# lcr_meter1.net
KiCad netlist of a schematic drawn in EAGLE
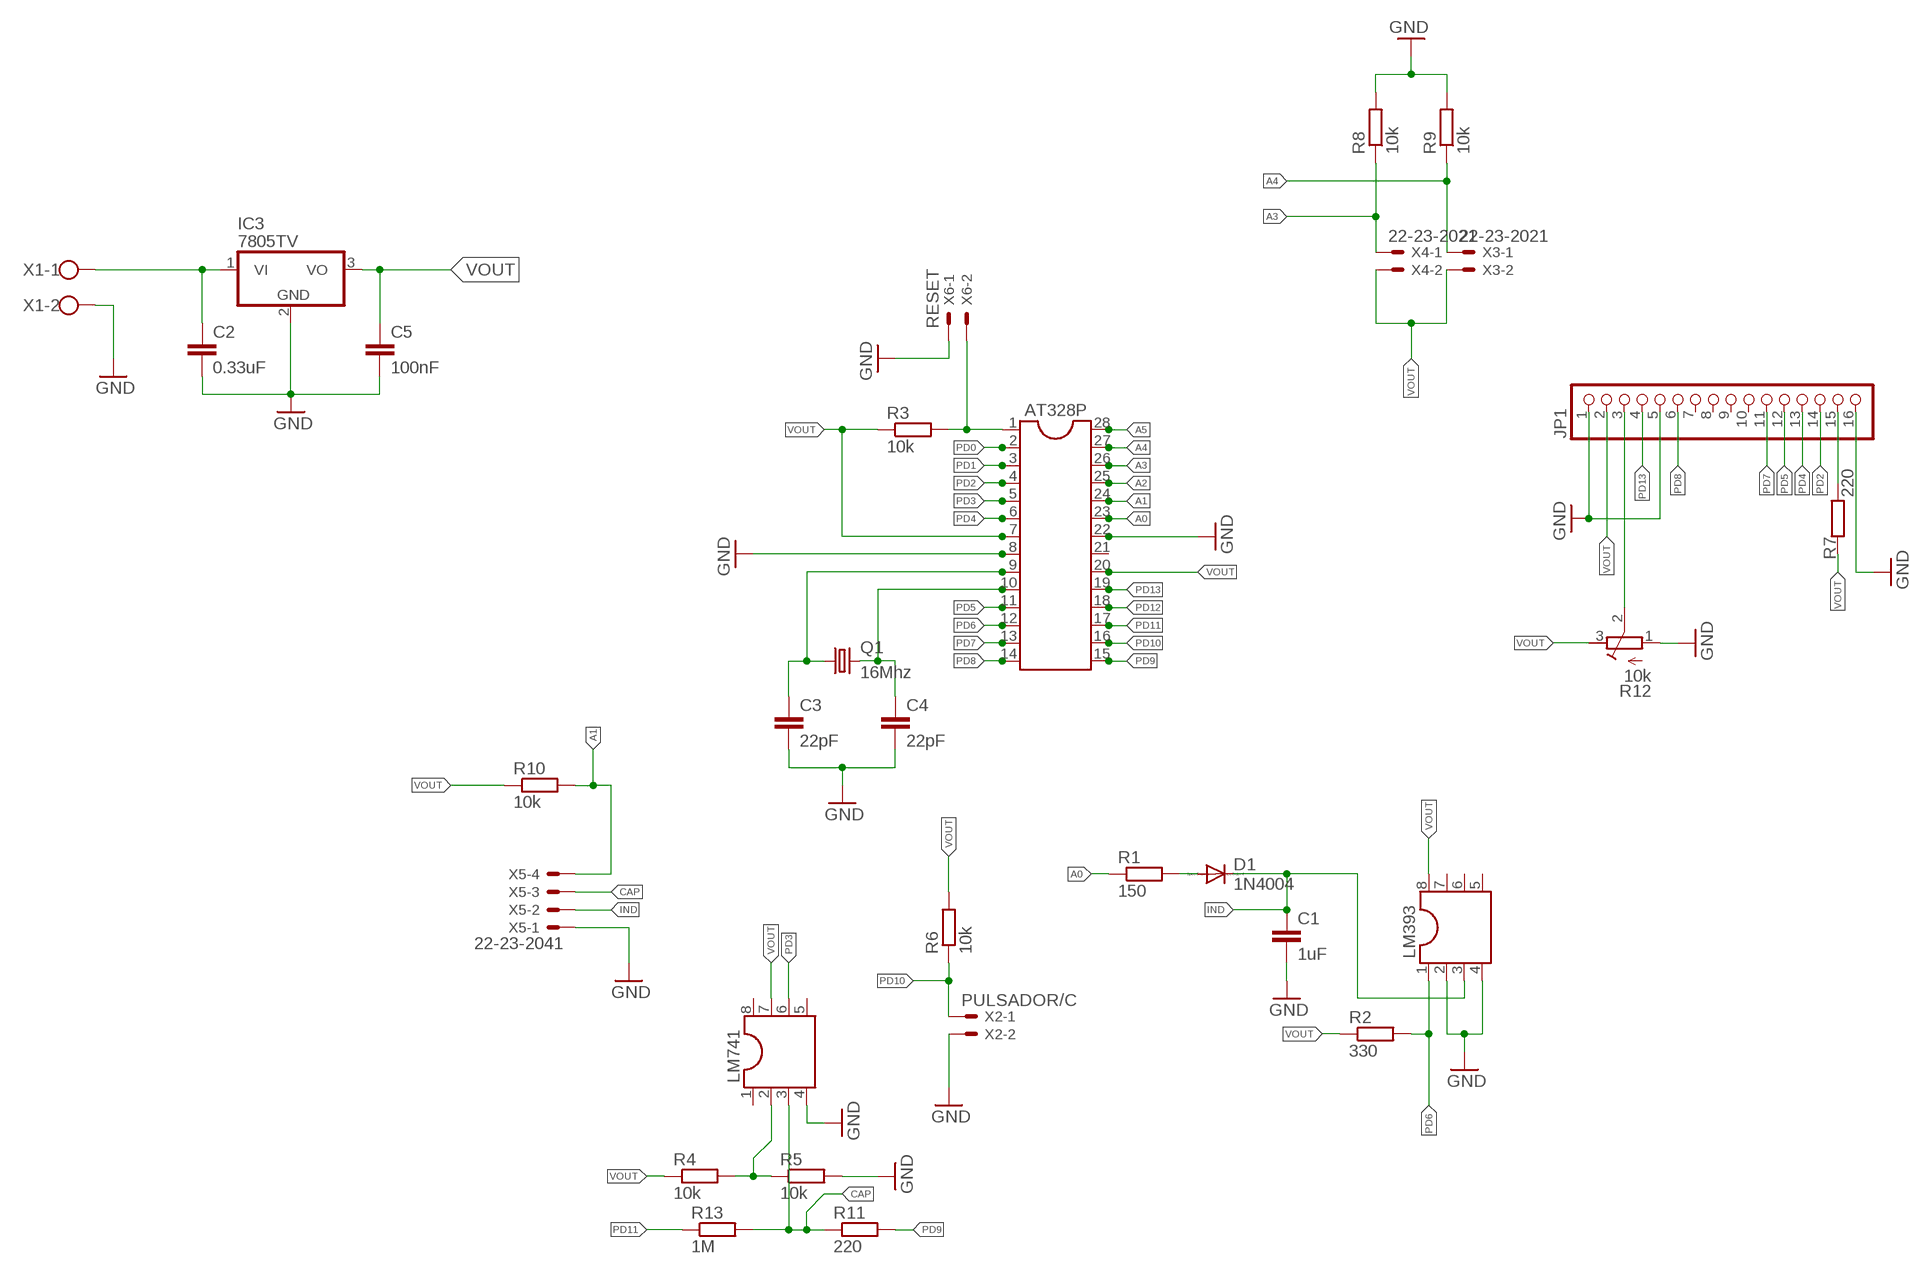
[diagram p0: schematic, sheet 1]

(export (version "E")
  (design (tool "Eeschema 10.0.6"))
  (components
    (comp (ref "AT328P")
      (value "DIL28-3")
      (footprint "eagle-import:DIL28-3")
      (libsource (lib "eagle-import") (part "DIL28-3"))
    )
    (comp (ref "C1")
      (value "1uF")
      (footprint "eagle-import:C050-024X044")
      (libsource (lib "eagle-import") (part "C-EU050-024X044"))
    )
    (comp (ref "C2")
      (value "0.33uF")
      (footprint "eagle-import:C050-024X044")
      (libsource (lib "eagle-import") (part "C-EU050-024X044"))
    )
    (comp (ref "C3")
      (value "22pF")
      (footprint "eagle-import:C025-030X050")
      (libsource (lib "eagle-import") (part "C-EU025-030X050"))
    )
    (comp (ref "C4")
      (value "22pF")
      (footprint "eagle-import:C025-030X050")
      (libsource (lib "eagle-import") (part "C-EU025-030X050"))
    )
    (comp (ref "C5")
      (value "100nF")
      (footprint "eagle-import:C025-030X050")
      (libsource (lib "eagle-import") (part "C-EU025-030X050"))
    )
    (comp (ref "D1")
      (value "1N4004")
      (footprint "eagle-import:DO41-10")
      (libsource (lib "eagle-import") (part "1N4004"))
    )
    (comp (ref "IC3")
      (value "7805TV")
      (footprint "eagle-import:TO220V")
      (libsource (lib "eagle-import") (part "78TV05"))
    )
    (comp (ref "JP1")
      (value "PINHD-1X16")
      (footprint "eagle-import:1X16")
      (libsource (lib "eagle-import") (part "PINHD-1X16"))
    )
    (comp (ref "LM393")
      (value "DIL8S")
      (footprint "eagle-import:SOCKET-08")
      (libsource (lib "eagle-import") (part "DIL8S"))
    )
    (comp (ref "LM741")
      (value "DIL8S")
      (footprint "eagle-import:SOCKET-08")
      (libsource (lib "eagle-import") (part "DIL8S"))
    )
    (comp (ref "Q1")
      (value "16Mhz")
      (footprint "eagle-import:HC49_S")
      (libsource (lib "eagle-import") (part "CRYSTALHC49S"))
    )
    (comp (ref "R1")
      (value "150")
      (footprint "eagle-import:0207_7")
      (libsource (lib "eagle-import") (part "R-EU_0207/7"))
    )
    (comp (ref "R2")
      (value "330")
      (footprint "eagle-import:0207_7")
      (libsource (lib "eagle-import") (part "R-EU_0207/7"))
    )
    (comp (ref "R3")
      (value "10k")
      (footprint "eagle-import:0207_7")
      (libsource (lib "eagle-import") (part "R-EU_0207/7"))
    )
    (comp (ref "R4")
      (value "10k")
      (footprint "eagle-import:0207_7")
      (libsource (lib "eagle-import") (part "R-EU_0207/7"))
    )
    (comp (ref "R5")
      (value "10k")
      (footprint "eagle-import:0207_7")
      (libsource (lib "eagle-import") (part "R-EU_0207/7"))
    )
    (comp (ref "R6")
      (value "10k")
      (footprint "eagle-import:0207_7")
      (libsource (lib "eagle-import") (part "R-EU_0207/7"))
    )
    (comp (ref "R7")
      (value "220")
      (footprint "eagle-import:0207_7")
      (libsource (lib "eagle-import") (part "R-EU_0207/7"))
    )
    (comp (ref "R8")
      (value "10k")
      (footprint "eagle-import:0207_7")
      (libsource (lib "eagle-import") (part "R-EU_0207/7"))
    )
    (comp (ref "R9")
      (value "10k")
      (footprint "eagle-import:0207_7")
      (libsource (lib "eagle-import") (part "R-EU_0207/7"))
    )
    (comp (ref "R10")
      (value "10k")
      (footprint "eagle-import:0207_7")
      (libsource (lib "eagle-import") (part "R-EU_0207/7"))
    )
    (comp (ref "R11")
      (value "220")
      (footprint "eagle-import:0207_7")
      (libsource (lib "eagle-import") (part "R-EU_0207/7"))
    )
    (comp (ref "R12")
      (value "10k")
      (footprint "eagle-import:RTRIM64W")
      (libsource (lib "eagle-import") (part "R-TRIMM64W"))
    )
    (comp (ref "R13")
      (value "1M")
      (footprint "eagle-import:0207_7")
      (libsource (lib "eagle-import") (part "R-EU_0207/7"))
    )
    (comp (ref "X1")
      (value "W237-102")
      (footprint "eagle-import:W237-102")
      (fields (field (name "MPN") "237-102"))
      (libsource (lib "eagle-import") (part "W237-102"))
    )
    (comp (ref "X2")
      (value "PULSADOR/C")
      (footprint "eagle-import:22-23-2021")
      (fields (field (name "MF") "MOLEX") (field (name "MPN") "22-23-2021"))
      (libsource (lib "eagle-import") (part "22-23-2021"))
    )
    (comp (ref "X3")
      (value "22-23-2021")
      (footprint "eagle-import:22-23-2021")
      (fields (field (name "MF") "MOLEX"))
      (libsource (lib "eagle-import") (part "22-23-2021"))
    )
    (comp (ref "X4")
      (value "22-23-2021")
      (footprint "eagle-import:22-23-2021")
      (fields (field (name "MF") "MOLEX"))
      (libsource (lib "eagle-import") (part "22-23-2021"))
    )
    (comp (ref "X5")
      (value "22-23-2041")
      (footprint "eagle-import:22-23-2041")
      (fields (field (name "MF") "MOLEX"))
      (libsource (lib "eagle-import") (part "22-23-2041"))
    )
    (comp (ref "X6")
      (value "RESET")
      (footprint "eagle-import:22-23-2021")
      (fields (field (name "MF") "MOLEX") (field (name "MPN") "22-23-2021"))
      (libsource (lib "eagle-import") (part "22-23-2021"))
    )
  )
  (nets
    (net (code "1") (name "A0") (class "Default")
      (node (ref "AT328P") (pin "23") (pinfunction "23_23") (pintype "passive"))
      (node (ref "R1") (pin "1") (pinfunction "1_1") (pintype "passive"))
    )
    (net (code "2") (name "A1") (class "Default")
      (node (ref "AT328P") (pin "24") (pinfunction "24_24") (pintype "passive"))
      (node (ref "R10") (pin "2") (pinfunction "2_2") (pintype "passive"))
      (node (ref "X5") (pin "4") (pinfunction "S_4") (pintype "passive"))
    )
    (net (code "3") (name "A2") (class "Default")
      (node (ref "AT328P") (pin "25") (pinfunction "25_25") (pintype "passive"))
    )
    (net (code "4") (name "A3") (class "Default")
      (node (ref "AT328P") (pin "26") (pinfunction "26_26") (pintype "passive"))
      (node (ref "R8") (pin "1") (pinfunction "1_1") (pintype "passive"))
      (node (ref "X4") (pin "1") (pinfunction "S_1") (pintype "passive"))
    )
    (net (code "5") (name "A4") (class "Default")
      (node (ref "AT328P") (pin "27") (pinfunction "27_27") (pintype "passive"))
      (node (ref "R9") (pin "1") (pinfunction "1_1") (pintype "passive"))
      (node (ref "X3") (pin "1") (pinfunction "S_1") (pintype "passive"))
    )
    (net (code "6") (name "A5") (class "Default")
      (node (ref "AT328P") (pin "28") (pinfunction "28_28") (pintype "passive"))
    )
    (net (code "7") (name "CAP") (class "Default")
      (node (ref "LM741") (pin "3") (pinfunction "3_3") (pintype "passive"))
      (node (ref "R11") (pin "1") (pinfunction "1_1") (pintype "passive"))
      (node (ref "R13") (pin "2") (pinfunction "2_2") (pintype "passive"))
      (node (ref "X5") (pin "3") (pinfunction "S_3") (pintype "passive"))
    )
    (net (code "8") (name "GND") (class "Default")
      (node (ref "AT328P") (pin "22") (pinfunction "22_22") (pintype "passive"))
      (node (ref "AT328P") (pin "8") (pinfunction "8_8") (pintype "passive"))
      (node (ref "C1") (pin "2") (pinfunction "2_2") (pintype "passive"))
      (node (ref "C2") (pin "2") (pinfunction "2_2") (pintype "passive"))
      (node (ref "C3") (pin "2") (pinfunction "2_2") (pintype "passive"))
      (node (ref "C4") (pin "2") (pinfunction "2_2") (pintype "passive"))
      (node (ref "C5") (pin "2") (pinfunction "2_2") (pintype "passive"))
      (node (ref "IC3") (pin "2") (pinfunction "GND_2") (pintype "passive"))
      (node (ref "JP1") (pin "1") (pinfunction "1_1") (pintype "passive"))
      (node (ref "JP1") (pin "16") (pinfunction "16_16") (pintype "passive"))
      (node (ref "JP1") (pin "5") (pinfunction "5_5") (pintype "passive"))
      (node (ref "LM393") (pin "2") (pinfunction "2_2") (pintype "passive"))
      (node (ref "LM393") (pin "4") (pinfunction "4_4") (pintype "passive"))
      (node (ref "LM741") (pin "4") (pinfunction "4_4") (pintype "passive"))
      (node (ref "R12") (pin "1") (pinfunction "A_1") (pintype "passive"))
      (node (ref "R5") (pin "2") (pinfunction "2_2") (pintype "passive"))
      (node (ref "R8") (pin "2") (pinfunction "2_2") (pintype "passive"))
      (node (ref "R9") (pin "2") (pinfunction "2_2") (pintype "passive"))
      (node (ref "X1") (pin "2") (pinfunction "KL_2") (pintype "passive"))
      (node (ref "X2") (pin "2") (pinfunction "S_2") (pintype "passive"))
      (node (ref "X5") (pin "1") (pinfunction "S_1") (pintype "passive"))
      (node (ref "X6") (pin "1") (pinfunction "S_1") (pintype "passive"))
    )
    (net (code "9") (name "IND") (class "Default")
      (node (ref "C1") (pin "1") (pinfunction "1_1") (pintype "passive"))
      (node (ref "D1") (pin "C") (pinfunction "C_C") (pintype "passive"))
      (node (ref "LM393") (pin "3") (pinfunction "3_3") (pintype "passive"))
      (node (ref "X5") (pin "2") (pinfunction "S_2") (pintype "passive"))
    )
    (net (code "10") (name "Net-(AT328P-Pad9)") (class "Default")
      (node (ref "AT328P") (pin "9") (pinfunction "9_9") (pintype "passive"))
      (node (ref "C3") (pin "1") (pinfunction "1_1") (pintype "passive"))
      (node (ref "Q1") (pin "1") (pinfunction "1_1") (pintype "passive"))
    )
    (net (code "11") (name "Net-(AT328P-Pad10)") (class "Default")
      (node (ref "AT328P") (pin "10") (pinfunction "10_10") (pintype "passive"))
      (node (ref "C4") (pin "1") (pinfunction "1_1") (pintype "passive"))
      (node (ref "Q1") (pin "2") (pinfunction "2_2") (pintype "passive"))
    )
    (net (code "12") (name "Net-(D1-PadA)") (class "Default")
      (node (ref "D1") (pin "A") (pinfunction "A_A") (pintype "passive"))
      (node (ref "R1") (pin "2") (pinfunction "2_2") (pintype "passive"))
    )
    (net (code "13") (name "Net-(IC3-VI)") (class "Default")
      (node (ref "C2") (pin "1") (pinfunction "1_1") (pintype "passive"))
      (node (ref "IC3") (pin "1") (pinfunction "VI_1") (pintype "input"))
      (node (ref "X1") (pin "1") (pinfunction "KL_1") (pintype "passive"))
    )
    (net (code "14") (name "Net-(JP1-Pad15)") (class "Default")
      (node (ref "JP1") (pin "15") (pinfunction "15_15") (pintype "passive"))
      (node (ref "R7") (pin "2") (pinfunction "2_2") (pintype "passive"))
    )
    (net (code "15") (name "Net-(LM741-Pad2)") (class "Default")
      (node (ref "LM741") (pin "2") (pinfunction "2_2") (pintype "passive"))
      (node (ref "R4") (pin "2") (pinfunction "2_2") (pintype "passive"))
      (node (ref "R5") (pin "1") (pinfunction "1_1") (pintype "passive"))
    )
    (net (code "16") (name "Net-(R12-S)") (class "Default")
      (node (ref "JP1") (pin "3") (pinfunction "3_3") (pintype "passive"))
      (node (ref "R12") (pin "2") (pinfunction "S_2") (pintype "passive"))
    )
    (net (code "17") (name "Net-(X6B-S)") (class "Default")
      (node (ref "AT328P") (pin "1") (pinfunction "1_1") (pintype "passive"))
      (node (ref "R3") (pin "2") (pinfunction "2_2") (pintype "passive"))
      (node (ref "X6") (pin "2") (pinfunction "S_2") (pintype "passive"))
    )
    (net (code "18") (name "PD0") (class "Default")
      (node (ref "AT328P") (pin "2") (pinfunction "2_2") (pintype "passive"))
    )
    (net (code "19") (name "PD1") (class "Default")
      (node (ref "AT328P") (pin "3") (pinfunction "3_3") (pintype "passive"))
    )
    (net (code "20") (name "PD2") (class "Default")
      (node (ref "AT328P") (pin "4") (pinfunction "4_4") (pintype "passive"))
      (node (ref "JP1") (pin "14") (pinfunction "14_14") (pintype "passive"))
    )
    (net (code "21") (name "PD3") (class "Default")
      (node (ref "AT328P") (pin "5") (pinfunction "5_5") (pintype "passive"))
      (node (ref "LM741") (pin "6") (pinfunction "6_6") (pintype "passive"))
    )
    (net (code "22") (name "PD4") (class "Default")
      (node (ref "AT328P") (pin "6") (pinfunction "6_6") (pintype "passive"))
      (node (ref "JP1") (pin "13") (pinfunction "13_13") (pintype "passive"))
    )
    (net (code "23") (name "PD5") (class "Default")
      (node (ref "AT328P") (pin "11") (pinfunction "11_11") (pintype "passive"))
      (node (ref "JP1") (pin "12") (pinfunction "12_12") (pintype "passive"))
    )
    (net (code "24") (name "PD6") (class "Default")
      (node (ref "AT328P") (pin "12") (pinfunction "12_12") (pintype "passive"))
      (node (ref "LM393") (pin "1") (pinfunction "1_1") (pintype "passive"))
      (node (ref "R2") (pin "2") (pinfunction "2_2") (pintype "passive"))
    )
    (net (code "25") (name "PD7") (class "Default")
      (node (ref "AT328P") (pin "13") (pinfunction "13_13") (pintype "passive"))
      (node (ref "JP1") (pin "11") (pinfunction "11_11") (pintype "passive"))
    )
    (net (code "26") (name "PD8") (class "Default")
      (node (ref "AT328P") (pin "14") (pinfunction "14_14") (pintype "passive"))
      (node (ref "JP1") (pin "6") (pinfunction "6_6") (pintype "passive"))
    )
    (net (code "27") (name "PD9") (class "Default")
      (node (ref "AT328P") (pin "15") (pinfunction "15_15") (pintype "passive"))
      (node (ref "R11") (pin "2") (pinfunction "2_2") (pintype "passive"))
    )
    (net (code "28") (name "PD10") (class "Default")
      (node (ref "AT328P") (pin "16") (pinfunction "16_16") (pintype "passive"))
      (node (ref "R6") (pin "1") (pinfunction "1_1") (pintype "passive"))
      (node (ref "X2") (pin "1") (pinfunction "S_1") (pintype "passive"))
    )
    (net (code "29") (name "PD11") (class "Default")
      (node (ref "AT328P") (pin "17") (pinfunction "17_17") (pintype "passive"))
      (node (ref "R13") (pin "1") (pinfunction "1_1") (pintype "passive"))
    )
    (net (code "30") (name "PD12") (class "Default")
      (node (ref "AT328P") (pin "18") (pinfunction "18_18") (pintype "passive"))
    )
    (net (code "31") (name "PD13") (class "Default")
      (node (ref "AT328P") (pin "19") (pinfunction "19_19") (pintype "passive"))
      (node (ref "JP1") (pin "4") (pinfunction "4_4") (pintype "passive"))
    )
    (net (code "32") (name "VOUT") (class "Default")
      (node (ref "AT328P") (pin "20") (pinfunction "20_20") (pintype "passive"))
      (node (ref "AT328P") (pin "7") (pinfunction "7_7") (pintype "passive"))
      (node (ref "C5") (pin "1") (pinfunction "1_1") (pintype "passive"))
      (node (ref "IC3") (pin "3") (pinfunction "VO_3") (pintype "passive"))
      (node (ref "JP1") (pin "2") (pinfunction "2_2") (pintype "passive"))
      (node (ref "LM393") (pin "8") (pinfunction "8_8") (pintype "passive"))
      (node (ref "LM741") (pin "7") (pinfunction "7_7") (pintype "passive"))
      (node (ref "R10") (pin "1") (pinfunction "1_1") (pintype "passive"))
      (node (ref "R12") (pin "3") (pinfunction "E_3") (pintype "passive"))
      (node (ref "R2") (pin "1") (pinfunction "1_1") (pintype "passive"))
      (node (ref "R3") (pin "1") (pinfunction "1_1") (pintype "passive"))
      (node (ref "R4") (pin "1") (pinfunction "1_1") (pintype "passive"))
      (node (ref "R6") (pin "2") (pinfunction "2_2") (pintype "passive"))
      (node (ref "R7") (pin "1") (pinfunction "1_1") (pintype "passive"))
      (node (ref "X3") (pin "2") (pinfunction "S_2") (pintype "passive"))
      (node (ref "X4") (pin "2") (pinfunction "S_2") (pintype "passive"))
    )
    (net (code "33") (name "unconnected-(AT328P-Pad21)") (class "Default")
      (node (ref "AT328P") (pin "21") (pinfunction "21_21") (pintype "passive"))
    )
    (net (code "34") (name "unconnected-(JP1-Pad7)") (class "Default")
      (node (ref "JP1") (pin "7") (pinfunction "7_7") (pintype "passive"))
    )
    (net (code "35") (name "unconnected-(JP1-Pad8)") (class "Default")
      (node (ref "JP1") (pin "8") (pinfunction "8_8") (pintype "passive"))
    )
    (net (code "36") (name "unconnected-(JP1-Pad9)") (class "Default")
      (node (ref "JP1") (pin "9") (pinfunction "9_9") (pintype "passive"))
    )
    (net (code "37") (name "unconnected-(JP1-Pad10)") (class "Default")
      (node (ref "JP1") (pin "10") (pinfunction "10_10") (pintype "passive"))
    )
    (net (code "38") (name "unconnected-(LM393-Pad5)") (class "Default")
      (node (ref "LM393") (pin "5") (pinfunction "5_5") (pintype "passive"))
    )
    (net (code "39") (name "unconnected-(LM393-Pad6)") (class "Default")
      (node (ref "LM393") (pin "6") (pinfunction "6_6") (pintype "passive"))
    )
    (net (code "40") (name "unconnected-(LM393-Pad7)") (class "Default")
      (node (ref "LM393") (pin "7") (pinfunction "7_7") (pintype "passive"))
    )
    (net (code "41") (name "unconnected-(LM741-Pad1)") (class "Default")
      (node (ref "LM741") (pin "1") (pinfunction "1_1") (pintype "passive"))
    )
    (net (code "42") (name "unconnected-(LM741-Pad5)") (class "Default")
      (node (ref "LM741") (pin "5") (pinfunction "5_5") (pintype "passive"))
    )
    (net (code "43") (name "unconnected-(LM741-Pad8)") (class "Default")
      (node (ref "LM741") (pin "8") (pinfunction "8_8") (pintype "passive"))
    )
  )
)
